# wifi-leds.net
KiCad netlist of a schematic drawn in EAGLE
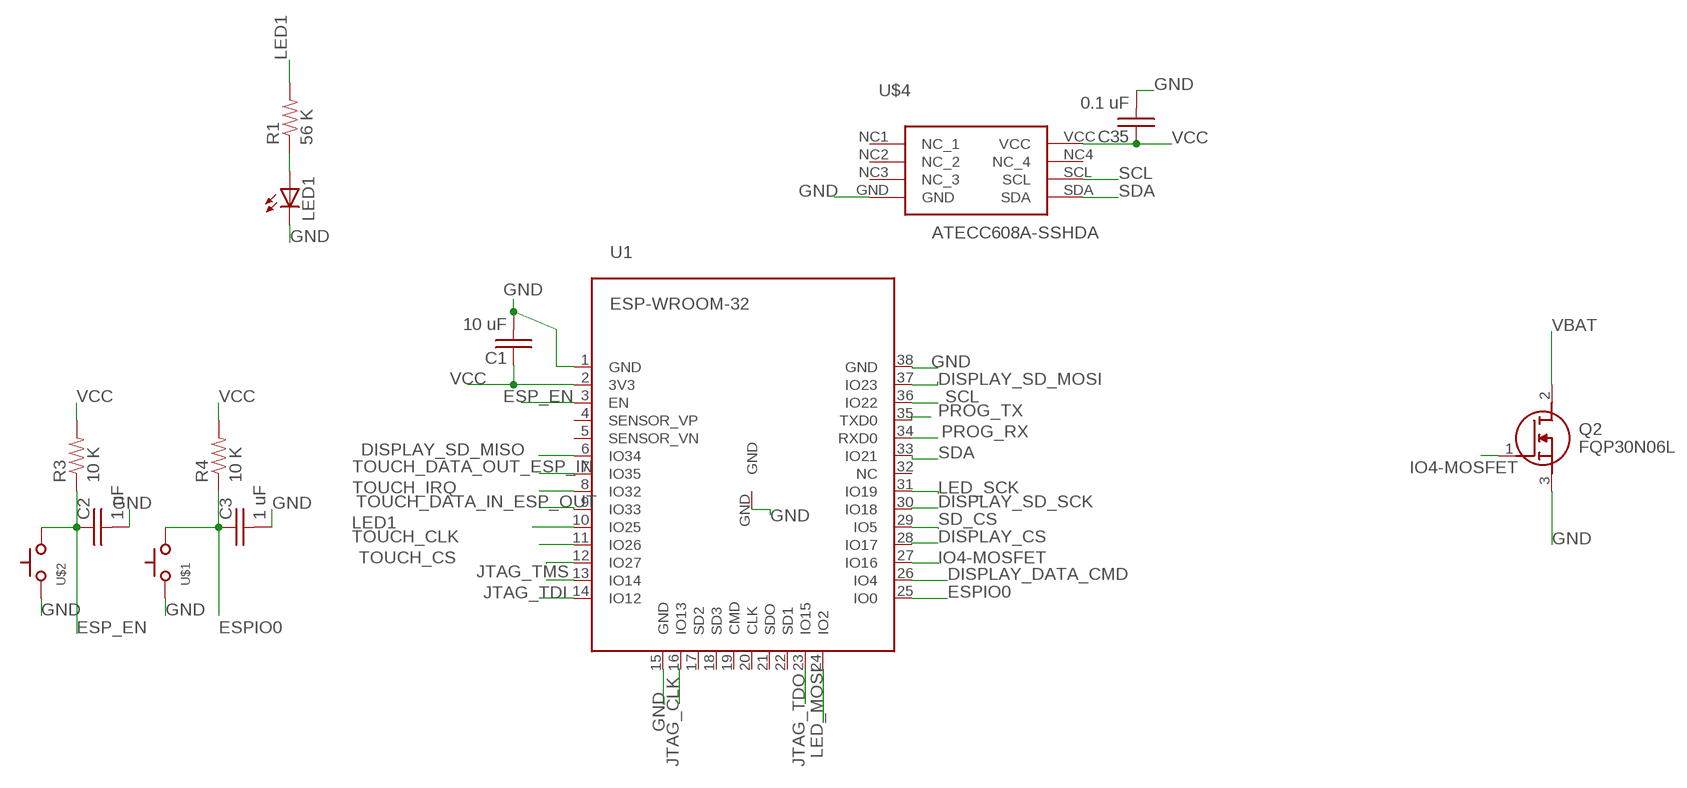
[diagram p0: schematic, sheet 1]
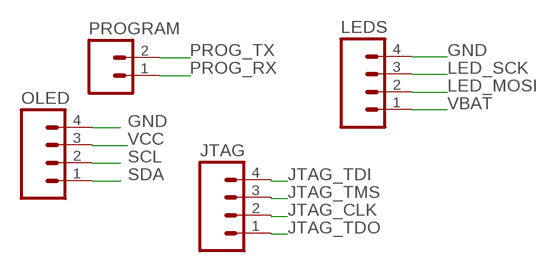
[diagram p1: schematic, sheet 2]
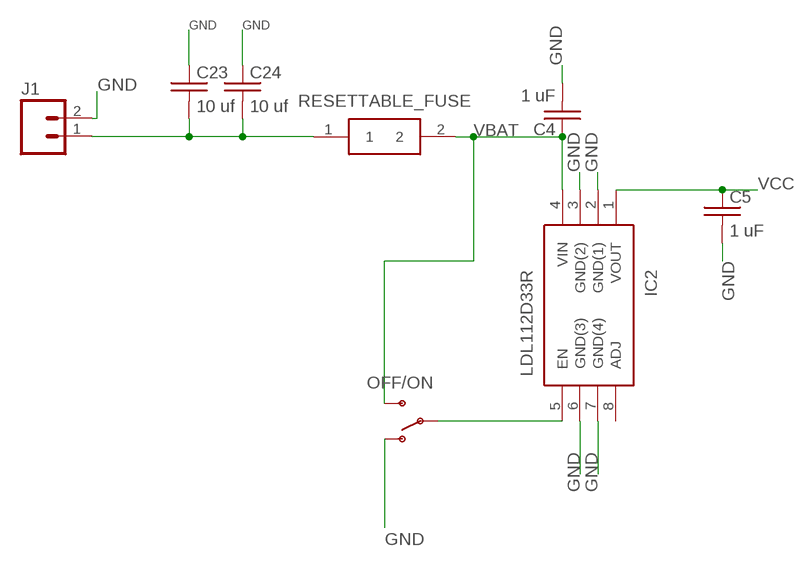
[diagram p2: schematic, sheet 3]
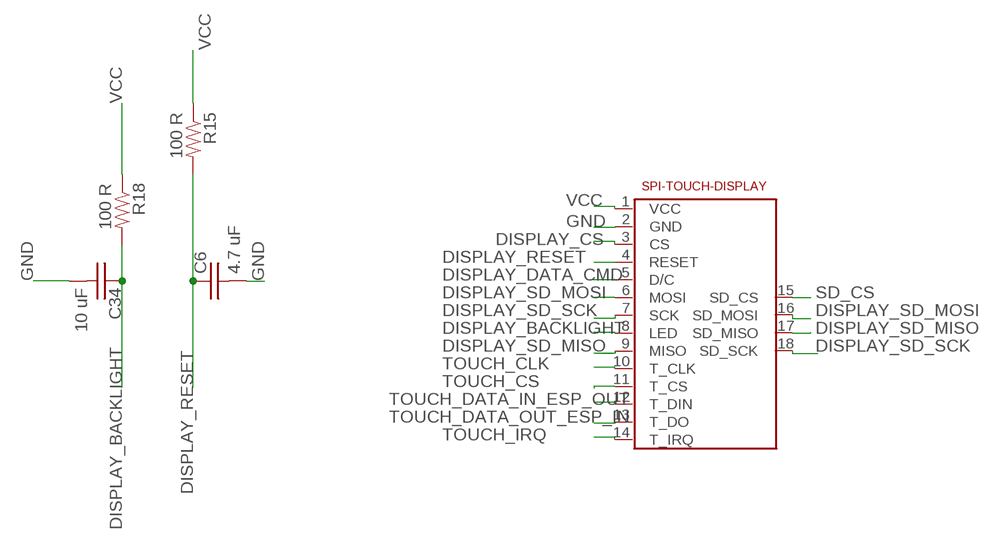
[diagram p3: schematic, sheet 4]
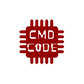
[diagram p4: schematic, sheet 5]

(export (version "E")
  (design (tool "Eeschema 10.0.6"))
  (components
    (comp (ref "U$5")
      (value "CMD_C0DE_LOGOCMD_CODE_LOGO_TOP_COPPER")
      (footprint "eagle-import:CMD_C0DE_LOGO_TOP_COPPER")
      (libsource (lib "eagle-import") (part "CMD_C0DE_LOGOCMD_CODE_LOGO_TOP_COPPER"))
    )
    (comp (ref "C6")
      (value "4.7 uF")
      (footprint "eagle-import:C0805")
      (libsource (lib "eagle-import") (part "C-USC0805"))
    )
    (comp (ref "C34")
      (value "10 uF")
      (footprint "eagle-import:C0805")
      (libsource (lib "eagle-import") (part "C-USC0805"))
    )
    (comp (ref "R15")
      (value "100 R")
      (footprint "eagle-import:0805")
      (libsource (lib "eagle-import") (part "RESISTOR0805-RES"))
    )
    (comp (ref "R18")
      (value "100 R")
      (footprint "eagle-import:0805")
      (libsource (lib "eagle-import") (part "RESISTOR0805-RES"))
    )
    (comp (ref "U$3")
      (value "2.4-SPI-TFT-TOUCH-SSD-MODULE")
      (footprint "eagle-import:2.4-SPI-TFT-TOUCH-SSD-MODULE")
      (libsource (lib "eagle-import") (part "2.4-SPI-TFT-TOUCH-SSD-MODULE"))
    )
    (comp (ref "C1")
      (value "10 uF")
      (footprint "eagle-import:C0805")
      (libsource (lib "eagle-import") (part "C-USC0805"))
    )
    (comp (ref "C2")
      (value "1 uF")
      (footprint "eagle-import:C0805")
      (libsource (lib "eagle-import") (part "C-USC0805"))
    )
    (comp (ref "C3")
      (value "1 uF")
      (footprint "eagle-import:C0805")
      (libsource (lib "eagle-import") (part "C-USC0805"))
    )
    (comp (ref "C35")
      (value "0.1 uF")
      (footprint "eagle-import:C0805")
      (libsource (lib "eagle-import") (part "C-USC0805"))
    )
    (comp (ref "LED1")
      (value "LED3MM")
      (footprint "eagle-import:LED3MM")
      (libsource (lib "eagle-import") (part "LED3MM"))
    )
    (comp (ref "Q2")
      (value "FQP30N06L")
      (footprint "eagle-import:TO254P470X1016X2019-3P")
      (fields (field (name "MOUSER_PART_NUMBER") "512-FQP30N06L") (field (name "RS_PART_NUMBER") "8075863P"))
      (libsource (lib "eagle-import") (part "FQP30N06L"))
    )
    (comp (ref "R1")
      (value "56 K")
      (footprint "eagle-import:0805")
      (libsource (lib "eagle-import") (part "passives_RESISTOR0805-RES"))
    )
    (comp (ref "R3")
      (value "10 K")
      (footprint "eagle-import:0805")
      (libsource (lib "eagle-import") (part "passives_RESISTOR0805-RES"))
    )
    (comp (ref "R4")
      (value "10 K")
      (footprint "eagle-import:0805")
      (libsource (lib "eagle-import") (part "passives_RESISTOR0805-RES"))
    )
    (comp (ref "U$1")
      (value "SWITCH_TACTILETACTILE-2PIN-NARROW")
      (footprint "eagle-import:TACTILE-2PIN-NARROW")
      (libsource (lib "eagle-import") (part "SWITCH_TACTILETACTILE-2PIN-NARROW"))
    )
    (comp (ref "U$2")
      (value "SWITCH_TACTILETACTILE-2PIN-NARROW")
      (footprint "eagle-import:TACTILE-2PIN-NARROW")
      (libsource (lib "eagle-import") (part "SWITCH_TACTILETACTILE-2PIN-NARROW"))
    )
    (comp (ref "U$4")
      (value "ATECC608A-SSHDA")
      (footprint "eagle-import:8-SOIC")
      (libsource (lib "eagle-import") (part "ATECC608A-SSHDA"))
    )
    (comp (ref "U1")
      (value "ESP-WROOM-32")
      (footprint "eagle-import:ESP-WROOM-32")
      (libsource (lib "eagle-import") (part "ESP-WROOM-32"))
    )
    (comp (ref "JTAG")
      (value "M04PTH")
      (footprint "eagle-import:1X04")
      (libsource (lib "eagle-import") (part "M04PTH"))
    )
    (comp (ref "LEDS")
      (value "M04POLAR")
      (footprint "eagle-import:MOLEX-1X4")
      (libsource (lib "eagle-import") (part "M04POLAR"))
    )
    (comp (ref "OLED")
      (value "M04PTH")
      (footprint "eagle-import:1X04")
      (libsource (lib "eagle-import") (part "M04PTH"))
    )
    (comp (ref "PROGRAM")
      (value "M02PTH")
      (footprint "eagle-import:1X02")
      (libsource (lib "eagle-import") (part "M02PTH"))
    )
    (comp (ref "C4")
      (value "1 uF")
      (footprint "eagle-import:C0805")
      (libsource (lib "eagle-import") (part "C-USC0805"))
    )
    (comp (ref "C5")
      (value "1 uF")
      (footprint "eagle-import:C0805")
      (libsource (lib "eagle-import") (part "C-USC0805"))
    )
    (comp (ref "C23")
      (value "10 uf")
      (footprint "eagle-import:C0805")
      (libsource (lib "eagle-import") (part "C-USC0805"))
    )
    (comp (ref "C24")
      (value "10 uf")
      (footprint "eagle-import:C0805")
      (libsource (lib "eagle-import") (part "C-USC0805"))
    )
    (comp (ref "IC2")
      (value "LDL112D33R")
      (footprint "eagle-import:SOIC127P600X175-8N")
      (libsource (lib "eagle-import") (part "LDL112D33R"))
    )
    (comp (ref "J1")
      (value "M02PTH")
      (footprint "eagle-import:1X02")
      (libsource (lib "eagle-import") (part "M02PTH"))
    )
    (comp (ref "OFF/ON")
      (value "SWITCH-SPSTKIT")
      (footprint "eagle-import:SWITCH-SPDT_KIT")
      (libsource (lib "eagle-import") (part "SWITCH-SPSTKIT"))
    )
    (comp (ref "RESETTABLE_FUSE")
      (value "0ZCJ0050FF2G")
      (footprint "eagle-import:FUSC3216X55N")
      (libsource (lib "eagle-import") (part "0ZCJ0050FF2G"))
    )
  )
  (nets
    (net (code "1") (name "DISPLAY_BACKLIGHT") (class "Default")
      (node (ref "C34") (pin "1") (pinfunction "1_1") (pintype "passive"))
      (node (ref "R18") (pin "2") (pinfunction "2_2") (pintype "passive"))
      (node (ref "U$3") (pin "8") (pinfunction "LED_8") (pintype "bidirectional"))
    )
    (net (code "2") (name "DISPLAY_CS") (class "Default")
      (node (ref "U$3") (pin "3") (pinfunction "CS_3") (pintype "bidirectional"))
      (node (ref "U1") (pin "28") (pinfunction "IO17_28") (pintype "bidirectional"))
    )
    (net (code "3") (name "DISPLAY_DATA_CMD") (class "Default")
      (node (ref "U$3") (pin "5") (pinfunction "D/C_5") (pintype "bidirectional"))
      (node (ref "U1") (pin "26") (pinfunction "IO4_26") (pintype "bidirectional"))
    )
    (net (code "4") (name "DISPLAY_RESET") (class "Default")
      (node (ref "C6") (pin "1") (pinfunction "1_1") (pintype "passive"))
      (node (ref "R15") (pin "2") (pinfunction "2_2") (pintype "passive"))
      (node (ref "U$3") (pin "4") (pinfunction "RESET_4") (pintype "bidirectional"))
    )
    (net (code "5") (name "DISPLAY_SD_MISO") (class "Default")
      (node (ref "U$3") (pin "17") (pinfunction "SD_MISO_17") (pintype "bidirectional"))
      (node (ref "U$3") (pin "9") (pinfunction "MISO_9") (pintype "bidirectional"))
      (node (ref "U1") (pin "6") (pinfunction "IO34_6") (pintype "bidirectional"))
    )
    (net (code "6") (name "DISPLAY_SD_MOSI") (class "Default")
      (node (ref "U$3") (pin "16") (pinfunction "SD_MOSI_16") (pintype "bidirectional"))
      (node (ref "U$3") (pin "6") (pinfunction "MOSI_6") (pintype "bidirectional"))
      (node (ref "U1") (pin "37") (pinfunction "IO23_37") (pintype "bidirectional"))
    )
    (net (code "7") (name "DISPLAY_SD_SCK") (class "Default")
      (node (ref "U$3") (pin "18") (pinfunction "SD_SCK_18") (pintype "bidirectional"))
      (node (ref "U$3") (pin "7") (pinfunction "SCK_7") (pintype "bidirectional"))
      (node (ref "U1") (pin "30") (pinfunction "IO18_30") (pintype "bidirectional"))
    )
    (net (code "8") (name "ESPIO0") (class "Default")
      (node (ref "C3") (pin "1") (pinfunction "1_1") (pintype "passive"))
      (node (ref "R4") (pin "1") (pinfunction "1_1") (pintype "passive"))
      (node (ref "U$1") (pin "P$1") (pinfunction "A_P$1") (pintype "passive"))
      (node (ref "U1") (pin "25") (pinfunction "IO0_25") (pintype "bidirectional"))
    )
    (net (code "9") (name "ESP_EN") (class "Default")
      (node (ref "C2") (pin "1") (pinfunction "1_1") (pintype "passive"))
      (node (ref "R3") (pin "1") (pinfunction "1_1") (pintype "passive"))
      (node (ref "U$2") (pin "P$1") (pinfunction "A_P$1") (pintype "passive"))
      (node (ref "U1") (pin "3") (pinfunction "EN_3") (pintype "bidirectional"))
    )
    (net (code "10") (name "GND") (class "Default")
      (node (ref "C1") (pin "2") (pinfunction "2_2") (pintype "passive"))
      (node (ref "C2") (pin "2") (pinfunction "2_2") (pintype "passive"))
      (node (ref "C23") (pin "1") (pinfunction "1_1") (pintype "passive"))
      (node (ref "C24") (pin "1") (pinfunction "1_1") (pintype "passive"))
      (node (ref "C3") (pin "2") (pinfunction "2_2") (pintype "passive"))
      (node (ref "C34") (pin "2") (pinfunction "2_2") (pintype "passive"))
      (node (ref "C35") (pin "2") (pinfunction "2_2") (pintype "passive"))
      (node (ref "C4") (pin "2") (pinfunction "2_2") (pintype "passive"))
      (node (ref "C5") (pin "2") (pinfunction "2_2") (pintype "passive"))
      (node (ref "C6") (pin "2") (pinfunction "2_2") (pintype "passive"))
      (node (ref "IC2") (pin "2") (pinfunction "GND(1)_2") (pintype "bidirectional"))
      (node (ref "IC2") (pin "3") (pinfunction "GND(2)_3") (pintype "bidirectional"))
      (node (ref "IC2") (pin "6") (pinfunction "GND(3)_6") (pintype "bidirectional"))
      (node (ref "IC2") (pin "7") (pinfunction "GND(4)_7") (pintype "bidirectional"))
      (node (ref "J1") (pin "2") (pinfunction "2_2") (pintype "passive"))
      (node (ref "LED1") (pin "K") (pinfunction "C_K") (pintype "output"))
      (node (ref "LEDS") (pin "4") (pinfunction "4_4") (pintype "passive"))
      (node (ref "OFF/ON") (pin "1") (pinfunction "O_1") (pintype "passive"))
      (node (ref "OLED") (pin "4") (pinfunction "4_4") (pintype "passive"))
      (node (ref "Q2") (pin "3") (pinfunction "S_3") (pintype "bidirectional"))
      (node (ref "U$1") (pin "P$2") (pinfunction "C_P$2") (pintype "passive"))
      (node (ref "U$2") (pin "P$2") (pinfunction "C_P$2") (pintype "passive"))
      (node (ref "U$3") (pin "2") (pinfunction "GND_2") (pintype "power_in"))
      (node (ref "U$4") (pin "GND") (pinfunction "GND_GND") (pintype "power_in"))
      (node (ref "U1") (pin "1") (pinfunction "GND_1") (pintype "bidirectional"))
      (node (ref "U1") (pin "15") (pinfunction "GND_15") (pintype "bidirectional"))
      (node (ref "U1") (pin "38") (pinfunction "GND_38") (pintype "bidirectional"))
      (node (ref "U1") (pin "GND") (pinfunction "GND_GND") (pintype "bidirectional"))
    )
    (net (code "11") (name "IO4-MOSFET") (class "Default")
      (node (ref "Q2") (pin "1") (pinfunction "G_1") (pintype "bidirectional"))
      (node (ref "U1") (pin "27") (pinfunction "IO16_27") (pintype "bidirectional"))
    )
    (net (code "12") (name "JTAG_CLK") (class "Default")
      (node (ref "JTAG") (pin "2") (pinfunction "2_2") (pintype "passive"))
      (node (ref "U1") (pin "16") (pinfunction "IO13_16") (pintype "bidirectional"))
    )
    (net (code "13") (name "JTAG_TDI") (class "Default")
      (node (ref "JTAG") (pin "4") (pinfunction "4_4") (pintype "passive"))
      (node (ref "U1") (pin "14") (pinfunction "IO12_14") (pintype "bidirectional"))
    )
    (net (code "14") (name "JTAG_TDO") (class "Default")
      (node (ref "JTAG") (pin "1") (pinfunction "1_1") (pintype "passive"))
      (node (ref "U1") (pin "23") (pinfunction "IO15_23") (pintype "bidirectional"))
    )
    (net (code "15") (name "JTAG_TMS") (class "Default")
      (node (ref "JTAG") (pin "3") (pinfunction "3_3") (pintype "passive"))
      (node (ref "U1") (pin "13") (pinfunction "IO14_13") (pintype "bidirectional"))
    )
    (net (code "16") (name "LED1") (class "Default")
      (node (ref "R1") (pin "2") (pinfunction "2_2") (pintype "passive"))
      (node (ref "U1") (pin "10") (pinfunction "IO25_10") (pintype "bidirectional"))
    )
    (net (code "17") (name "LED_MOSI") (class "Default")
      (node (ref "LEDS") (pin "2") (pinfunction "2_2") (pintype "passive"))
      (node (ref "U1") (pin "24") (pinfunction "IO2_24") (pintype "bidirectional"))
    )
    (net (code "18") (name "LED_SCK") (class "Default")
      (node (ref "LEDS") (pin "3") (pinfunction "3_3") (pintype "passive"))
      (node (ref "U1") (pin "31") (pinfunction "IO19_31") (pintype "bidirectional"))
    )
    (net (code "19") (name "Net-(C23-Pad2)") (class "Default")
      (node (ref "C23") (pin "2") (pinfunction "2_2") (pintype "passive"))
      (node (ref "C24") (pin "2") (pinfunction "2_2") (pintype "passive"))
      (node (ref "J1") (pin "1") (pinfunction "1_1") (pintype "passive"))
      (node (ref "RESETTABLE_FUSE") (pin "1") (pinfunction "1_1") (pintype "passive"))
    )
    (net (code "20") (name "Net-(IC2-EN)") (class "Default")
      (node (ref "IC2") (pin "5") (pinfunction "EN_5") (pintype "bidirectional"))
      (node (ref "OFF/ON") (pin "2") (pinfunction "P_2") (pintype "passive"))
    )
    (net (code "21") (name "Net-(LED1-PadA)") (class "Default")
      (node (ref "LED1") (pin "A") (pinfunction "A_A") (pintype "input"))
      (node (ref "R1") (pin "1") (pinfunction "1_1") (pintype "passive"))
    )
    (net (code "22") (name "PROG_RX") (class "Default")
      (node (ref "PROGRAM") (pin "1") (pinfunction "1_1") (pintype "passive"))
      (node (ref "U1") (pin "34") (pinfunction "RXD0_34") (pintype "bidirectional"))
    )
    (net (code "23") (name "PROG_TX") (class "Default")
      (node (ref "PROGRAM") (pin "2") (pinfunction "2_2") (pintype "passive"))
      (node (ref "U1") (pin "35") (pinfunction "TXD0_35") (pintype "bidirectional"))
    )
    (net (code "24") (name "SCL") (class "Default")
      (node (ref "OLED") (pin "2") (pinfunction "2_2") (pintype "passive"))
      (node (ref "U$4") (pin "SCL") (pinfunction "SCL_SCL") (pintype "bidirectional"))
      (node (ref "U1") (pin "36") (pinfunction "IO22_36") (pintype "bidirectional"))
    )
    (net (code "25") (name "SDA") (class "Default")
      (node (ref "OLED") (pin "1") (pinfunction "1_1") (pintype "passive"))
      (node (ref "U$4") (pin "SDA") (pinfunction "SDA_SDA") (pintype "bidirectional"))
      (node (ref "U1") (pin "33") (pinfunction "IO21_33") (pintype "bidirectional"))
    )
    (net (code "26") (name "SD_CS") (class "Default")
      (node (ref "U$3") (pin "15") (pinfunction "SD_CS_15") (pintype "bidirectional"))
      (node (ref "U1") (pin "29") (pinfunction "IO5_29") (pintype "bidirectional"))
    )
    (net (code "27") (name "TOUCH_CLK") (class "Default")
      (node (ref "U$3") (pin "10") (pinfunction "T_CLK_10") (pintype "bidirectional"))
      (node (ref "U1") (pin "11") (pinfunction "IO26_11") (pintype "bidirectional"))
    )
    (net (code "28") (name "TOUCH_CS") (class "Default")
      (node (ref "U$3") (pin "11") (pinfunction "T_CS_11") (pintype "bidirectional"))
      (node (ref "U1") (pin "12") (pinfunction "IO27_12") (pintype "bidirectional"))
    )
    (net (code "29") (name "TOUCH_DATA_IN_ESP_OUT") (class "Default")
      (node (ref "U$3") (pin "12") (pinfunction "T_DIN_12") (pintype "bidirectional"))
      (node (ref "U1") (pin "9") (pinfunction "IO33_9") (pintype "bidirectional"))
    )
    (net (code "30") (name "TOUCH_DATA_OUT_ESP_IN") (class "Default")
      (node (ref "U$3") (pin "13") (pinfunction "T_DO_13") (pintype "bidirectional"))
      (node (ref "U1") (pin "7") (pinfunction "IO35_7") (pintype "bidirectional"))
    )
    (net (code "31") (name "TOUCH_IRQ") (class "Default")
      (node (ref "U$3") (pin "14") (pinfunction "T_IRQ_14") (pintype "bidirectional"))
      (node (ref "U1") (pin "8") (pinfunction "IO32_8") (pintype "bidirectional"))
    )
    (net (code "32") (name "VBAT") (class "Default")
      (node (ref "C4") (pin "1") (pinfunction "1_1") (pintype "passive"))
      (node (ref "IC2") (pin "4") (pinfunction "VIN_4") (pintype "bidirectional"))
      (node (ref "LEDS") (pin "1") (pinfunction "1_1") (pintype "passive"))
      (node (ref "OFF/ON") (pin "3") (pinfunction "S_3") (pintype "passive"))
      (node (ref "Q2") (pin "2") (pinfunction "D_2") (pintype "bidirectional"))
      (node (ref "RESETTABLE_FUSE") (pin "2") (pinfunction "2_2") (pintype "passive"))
    )
    (net (code "33") (name "VCC") (class "Default")
      (node (ref "C1") (pin "1") (pinfunction "1_1") (pintype "passive"))
      (node (ref "C35") (pin "1") (pinfunction "1_1") (pintype "passive"))
      (node (ref "C5") (pin "1") (pinfunction "1_1") (pintype "passive"))
      (node (ref "IC2") (pin "1") (pinfunction "VOUT_1") (pintype "bidirectional"))
      (node (ref "OLED") (pin "3") (pinfunction "3_3") (pintype "passive"))
      (node (ref "R15") (pin "1") (pinfunction "1_1") (pintype "passive"))
      (node (ref "R18") (pin "1") (pinfunction "1_1") (pintype "passive"))
      (node (ref "R3") (pin "2") (pinfunction "2_2") (pintype "passive"))
      (node (ref "R4") (pin "2") (pinfunction "2_2") (pintype "passive"))
      (node (ref "U$3") (pin "1") (pinfunction "VCC_1") (pintype "power_in"))
      (node (ref "U$4") (pin "VCC") (pinfunction "VCC_VCC") (pintype "power_in"))
      (node (ref "U1") (pin "2") (pinfunction "3V3_2") (pintype "bidirectional"))
    )
    (net (code "34") (name "unconnected-(IC2-ADJ-Pad8)") (class "Default")
      (node (ref "IC2") (pin "8") (pinfunction "ADJ_8") (pintype "bidirectional"))
    )
    (net (code "35") (name "unconnected-(U$4-NC_1-PadNC1)") (class "Default")
      (node (ref "U$4") (pin "NC1") (pinfunction "NC_1_NC1") (pintype "no_connect"))
    )
    (net (code "36") (name "unconnected-(U$4-NC_2-PadNC2)") (class "Default")
      (node (ref "U$4") (pin "NC2") (pinfunction "NC_2_NC2") (pintype "no_connect"))
    )
    (net (code "37") (name "unconnected-(U$4-NC_3-PadNC3)") (class "Default")
      (node (ref "U$4") (pin "NC3") (pinfunction "NC_3_NC3") (pintype "no_connect"))
    )
    (net (code "38") (name "unconnected-(U$4-NC_4-PadNC4)") (class "Default")
      (node (ref "U$4") (pin "NC4") (pinfunction "NC_4_NC4") (pintype "no_connect"))
    )
    (net (code "39") (name "unconnected-(U1-CLK-Pad20)") (class "Default")
      (node (ref "U1") (pin "20") (pinfunction "CLK_20") (pintype "bidirectional"))
    )
    (net (code "40") (name "unconnected-(U1-CMD-Pad19)") (class "Default")
      (node (ref "U1") (pin "19") (pinfunction "CMD_19") (pintype "bidirectional"))
    )
    (net (code "41") (name "unconnected-(U1-NC-Pad32)") (class "Default")
      (node (ref "U1") (pin "32") (pinfunction "NC_32") (pintype "bidirectional"))
    )
    (net (code "42") (name "unconnected-(U1-SD1-Pad22)") (class "Default")
      (node (ref "U1") (pin "22") (pinfunction "SD1_22") (pintype "bidirectional"))
    )
    (net (code "43") (name "unconnected-(U1-SD2-Pad17)") (class "Default")
      (node (ref "U1") (pin "17") (pinfunction "SD2_17") (pintype "bidirectional"))
    )
    (net (code "44") (name "unconnected-(U1-SD3-Pad18)") (class "Default")
      (node (ref "U1") (pin "18") (pinfunction "SD3_18") (pintype "bidirectional"))
    )
    (net (code "45") (name "unconnected-(U1-SDO-Pad21)") (class "Default")
      (node (ref "U1") (pin "21") (pinfunction "SDO_21") (pintype "bidirectional"))
    )
    (net (code "46") (name "unconnected-(U1-SENSOR_VN-Pad5)") (class "Default")
      (node (ref "U1") (pin "5") (pinfunction "SENSOR_VN_5") (pintype "bidirectional"))
    )
    (net (code "47") (name "unconnected-(U1-SENSOR_VP-Pad4)") (class "Default")
      (node (ref "U1") (pin "4") (pinfunction "SENSOR_VP_4") (pintype "bidirectional"))
    )
  )
)
